# GD32F450_Power_Manager_Camera__V1_0.net
KiCad netlist of a schematic drawn in Altium Designer
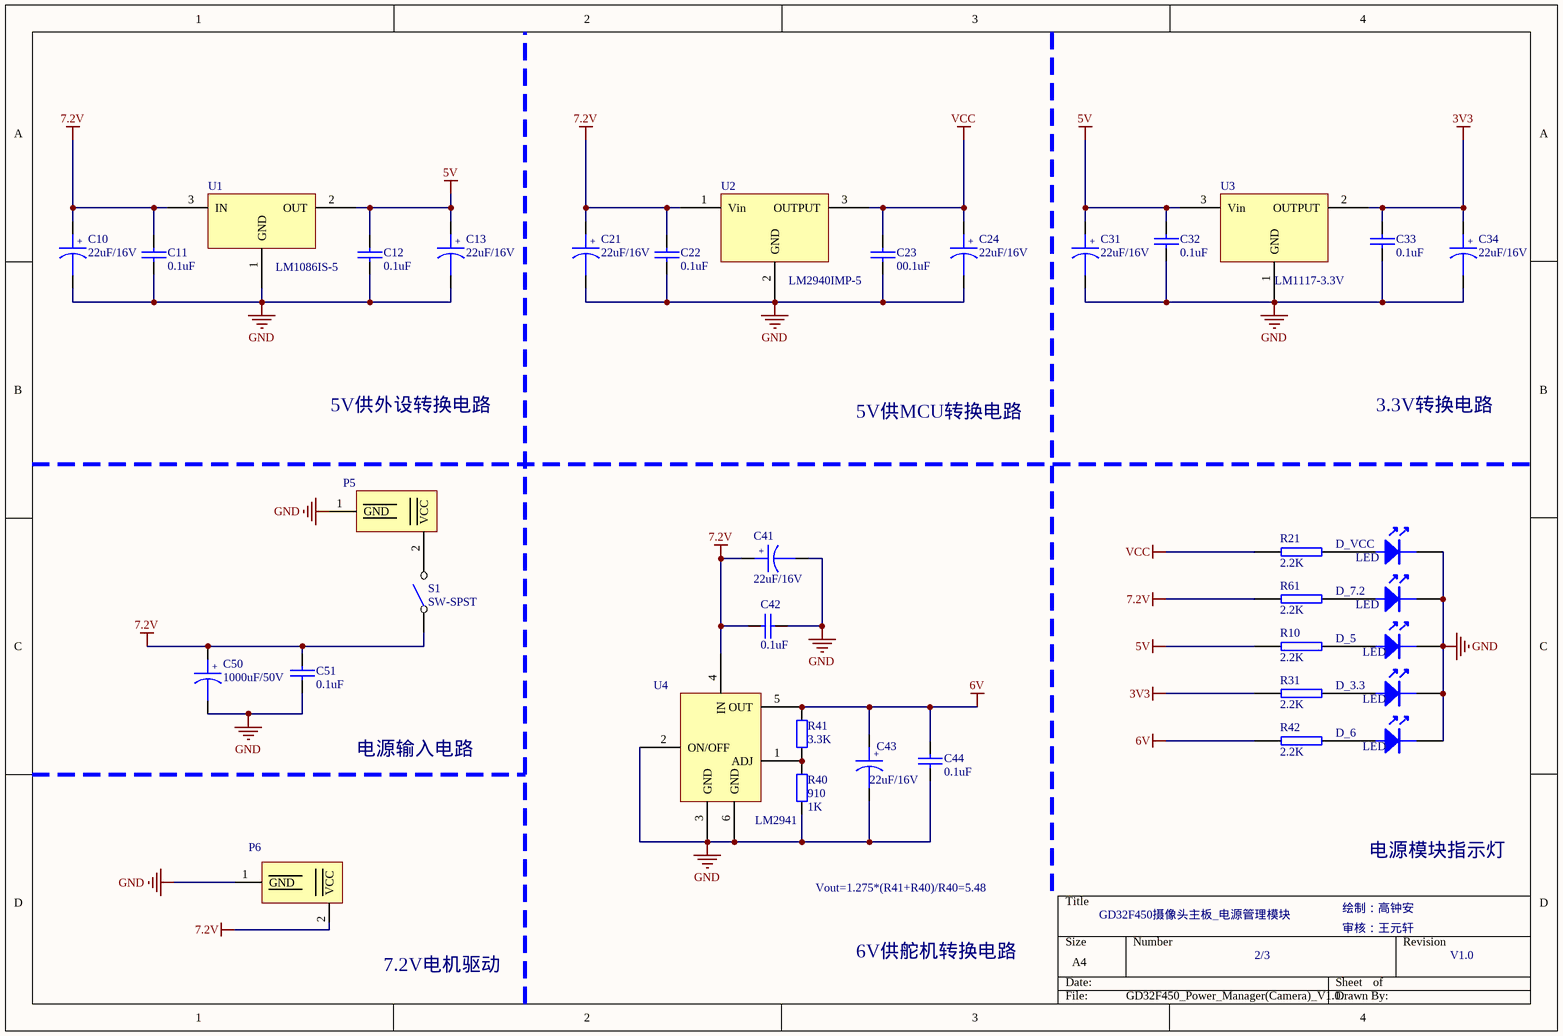
[diagram p0: GD32F450_Power_Manager(Camera)_V1.0.SchDoc]

(export (version "E")
  (design (tool "Eeschema 10.0.6"))
  (components
    (comp (ref "C10")
      (value "22uF/16V")
      (footprint "3528")
      (description "Capacitor")
      (libsource (lib "Protel99Lib_SCH") (part "CAPACITOR POL"))
    )
    (comp (ref "C11")
      (value "0.1uF")
      (footprint "0805C")
      (description "Capacitor")
      (libsource (lib "Protel99Lib_SCH") (part "CAP"))
    )
    (comp (ref "C12")
      (value "0.1uF")
      (footprint "0805C")
      (description "Capacitor")
      (libsource (lib "Protel99Lib_SCH") (part "CAP"))
    )
    (comp (ref "C13")
      (value "22uF/16V")
      (footprint "3528")
      (description "Capacitor")
      (libsource (lib "Protel99Lib_SCH") (part "CAPACITOR POL"))
    )
    (comp (ref "C21")
      (value "22uF/16V")
      (footprint "3528")
      (description "Capacitor")
      (libsource (lib "Protel99Lib_SCH") (part "CAPACITOR POL"))
    )
    (comp (ref "C22")
      (value "0.1uF")
      (footprint "0805C")
      (description "Capacitor")
      (libsource (lib "Protel99Lib_SCH") (part "CAP"))
    )
    (comp (ref "C23")
      (value "00.1uF")
      (footprint "0805C")
      (description "Capacitor")
      (libsource (lib "Protel99Lib_SCH") (part "CAP"))
    )
    (comp (ref "C24")
      (value "22uF/16V")
      (footprint "3528")
      (description "Capacitor")
      (libsource (lib "Protel99Lib_SCH") (part "CAPACITOR POL"))
    )
    (comp (ref "C31")
      (value "22uF/16V")
      (footprint "3528")
      (description "Capacitor")
      (libsource (lib "Protel99Lib_SCH") (part "CAPACITOR POL"))
    )
    (comp (ref "C32")
      (value "0.1uF")
      (footprint "0805C")
      (description "Capacitor")
      (libsource (lib "Protel99Lib_SCH") (part "CAP"))
    )
    (comp (ref "C33")
      (value "0.1uF")
      (footprint "0805C")
      (description "Capacitor")
      (libsource (lib "Protel99Lib_SCH") (part "CAP"))
    )
    (comp (ref "C34")
      (value "22uF/16V")
      (footprint "3528")
      (description "Capacitor")
      (libsource (lib "Protel99Lib_SCH") (part "CAPACITOR POL"))
    )
    (comp (ref "C41")
      (value "22uF/16V")
      (footprint "3528")
      (description "Capacitor")
      (libsource (lib "Protel99Lib_SCH") (part "CAPACITOR POL"))
    )
    (comp (ref "C42")
      (value "0.1uF")
      (footprint "0805C")
      (description "Capacitor")
      (libsource (lib "Protel99Lib_SCH") (part "CAP"))
    )
    (comp (ref "C43")
      (value "22uF/16V")
      (footprint "3528")
      (description "Capacitor")
      (libsource (lib "Protel99Lib_SCH") (part "CAPACITOR POL"))
    )
    (comp (ref "C44")
      (value "0.1uF")
      (footprint "0805C")
      (description "Capacitor")
      (libsource (lib "Protel99Lib_SCH") (part "CAP"))
    )
    (comp (ref "C50")
      (value "1000uF/50V")
      (footprint "CM F(10*10.2)")
      (description "Capacitor")
      (libsource (lib "Protel99Lib_SCH") (part "CAPACITOR POL"))
    )
    (comp (ref "C51")
      (value "0.1uF")
      (footprint "0805C")
      (description "Capacitor")
      (libsource (lib "Protel99Lib_SCH") (part "CAP"))
    )
    (comp (ref "D_3.3") (value "LED") (footprint "1206LED") (libsource (lib "Protel99Lib_SCH") (part "LED")))
    (comp (ref "D_5") (value "LED") (footprint "1206LED") (libsource (lib "Protel99Lib_SCH") (part "LED")))
    (comp (ref "D_6") (value "LED") (footprint "1206LED") (libsource (lib "Protel99Lib_SCH") (part "LED")))
    (comp (ref "D_7.2") (value "LED") (footprint "1206LED") (libsource (lib "Protel99Lib_SCH") (part "LED")))
    (comp (ref "D_VCC") (value "LED") (footprint "1206LED") (libsource (lib "Protel99Lib_SCH") (part "LED")))
    (comp (ref "P5")
      (value "T_Type_Adapter")
      (footprint "T_Type_Adapter")
      (libsource (lib "Schlib1") (part "T_Type_Adapter"))
    )
    (comp (ref "P6")
      (value "T_Type_Adapter")
      (footprint "T_Type_Adapter")
      (libsource (lib "Schlib1") (part "T_Type_Adapter"))
    )
    (comp (ref "R10") (value "2.2K") (footprint "0805R") (libsource (lib "Protel99Lib_SCH") (part "RES2")))
    (comp (ref "R21") (value "2.2K") (footprint "0805R") (libsource (lib "Protel99Lib_SCH") (part "RES2")))
    (comp (ref "R31") (value "2.2K") (footprint "0805R") (libsource (lib "Protel99Lib_SCH") (part "RES2")))
    (comp (ref "R40")
      (value "910")
      (footprint "0805")
      (description "Resistor")
      (fields (field (name "ALTIUM_VALUE") "1K") (field (name "PUBLISHER") "Altium Limited"))
      (libsource (lib "Miscellaneous Devices") (part "Res2"))
    )
    (comp (ref "R41")
      (value "3.3K")
      (footprint "0805")
      (description "Resistor")
      (fields (field (name "PUBLISHER") "Altium Limited"))
      (libsource (lib "Miscellaneous Devices") (part "Res2"))
    )
    (comp (ref "R42") (value "2.2K") (footprint "0805R") (libsource (lib "Protel99Lib_SCH") (part "RES2")))
    (comp (ref "R61") (value "2.2K") (footprint "0805R") (libsource (lib "Protel99Lib_SCH") (part "RES2")))
    (comp (ref "S1")
      (value "SW-SPST")
      (footprint "SWITCH-MINI")
      (libsource (lib "Protel99Lib_SCH") (part "SW-SPST"))
    )
    (comp (ref "U1")
      (value "LM1086IS-5")
      (footprint "TO263-3A")
      (libsource (lib "BaseLib_SCH") (part "LT1086"))
    )
    (comp (ref "U2") (value "LM2940IMP-5") (footprint "SOT-223") (libsource (lib "") (part "LM1117-3.3V_1")))
    (comp (ref "U3")
      (value "LM1117-3.3V")
      (footprint "SOT-223")
      (libsource (lib "BaseLib_SCH") (part "LM1117-3.3V"))
    )
    (comp (ref "U4")
      (value "LM2941")
      (footprint "TO-263")
      (libsource (lib "KEA128_Experiment_Platform") (part "LM2941"))
    )
  )
  (nets
    (net (code "1") (name "3V3") (class "Default")
      (node (ref "C33") (pin "1") (pinfunction "1_1") (pintype "passive"))
      (node (ref "C34") (pin "1") (pinfunction "1_1") (pintype "passive"))
      (node (ref "R31") (pin "1") (pinfunction "1_1") (pintype "passive"))
      (node (ref "U3") (pin "2") (pinfunction "OUTPUT_2") (pintype "passive"))
    )
    (net (code "2") (name "5V") (class "Default")
      (node (ref "C12") (pin "1") (pinfunction "1_1") (pintype "passive"))
      (node (ref "C13") (pin "1") (pinfunction "1_1") (pintype "passive"))
      (node (ref "C31") (pin "1") (pinfunction "1_1") (pintype "passive"))
      (node (ref "C32") (pin "1") (pinfunction "1_1") (pintype "passive"))
      (node (ref "R10") (pin "1") (pinfunction "1_1") (pintype "passive"))
      (node (ref "U1") (pin "2") (pinfunction "OUT_2") (pintype "passive"))
      (node (ref "U3") (pin "3") (pinfunction "Vin_3") (pintype "passive"))
    )
    (net (code "3") (name "6V") (class "Default")
      (node (ref "C43") (pin "1") (pinfunction "1_1") (pintype "passive"))
      (node (ref "C44") (pin "1") (pinfunction "1_1") (pintype "passive"))
      (node (ref "R41") (pin "2") (pinfunction "2_2") (pintype "passive"))
      (node (ref "R42") (pin "1") (pinfunction "1_1") (pintype "passive"))
      (node (ref "U4") (pin "5") (pinfunction "OUT_5") (pintype "passive"))
    )
    (net (code "4") (name "7.2V") (class "Default")
      (node (ref "C10") (pin "1") (pinfunction "1_1") (pintype "passive"))
      (node (ref "C11") (pin "1") (pinfunction "1_1") (pintype "passive"))
      (node (ref "C21") (pin "1") (pinfunction "1_1") (pintype "passive"))
      (node (ref "C22") (pin "1") (pinfunction "1_1") (pintype "passive"))
      (node (ref "C41") (pin "1") (pinfunction "1_1") (pintype "passive"))
      (node (ref "C42") (pin "1") (pinfunction "1_1") (pintype "passive"))
      (node (ref "C50") (pin "1") (pinfunction "1_1") (pintype "passive"))
      (node (ref "C51") (pin "1") (pinfunction "1_1") (pintype "passive"))
      (node (ref "P6") (pin "2") (pinfunction "VCC_2") (pintype "passive"))
      (node (ref "R61") (pin "1") (pinfunction "1_1") (pintype "passive"))
      (node (ref "S1") (pin "1") (pinfunction "1_1") (pintype "passive"))
      (node (ref "U1") (pin "3") (pinfunction "IN_3") (pintype "passive"))
      (node (ref "U2") (pin "1") (pinfunction "Vin_1") (pintype "passive"))
      (node (ref "U4") (pin "4") (pinfunction "IN_4") (pintype "passive"))
    )
    (net (code "5") (name "GND") (class "Default")
      (node (ref "C10") (pin "2") (pinfunction "2_2") (pintype "passive"))
      (node (ref "C11") (pin "2") (pinfunction "2_2") (pintype "passive"))
      (node (ref "C12") (pin "2") (pinfunction "2_2") (pintype "passive"))
      (node (ref "C13") (pin "2") (pinfunction "2_2") (pintype "passive"))
      (node (ref "C21") (pin "2") (pinfunction "2_2") (pintype "passive"))
      (node (ref "C22") (pin "2") (pinfunction "2_2") (pintype "passive"))
      (node (ref "C23") (pin "2") (pinfunction "2_2") (pintype "passive"))
      (node (ref "C24") (pin "2") (pinfunction "2_2") (pintype "passive"))
      (node (ref "C31") (pin "2") (pinfunction "2_2") (pintype "passive"))
      (node (ref "C32") (pin "2") (pinfunction "2_2") (pintype "passive"))
      (node (ref "C33") (pin "2") (pinfunction "2_2") (pintype "passive"))
      (node (ref "C34") (pin "2") (pinfunction "2_2") (pintype "passive"))
      (node (ref "C41") (pin "2") (pinfunction "2_2") (pintype "passive"))
      (node (ref "C42") (pin "2") (pinfunction "2_2") (pintype "passive"))
      (node (ref "C43") (pin "2") (pinfunction "2_2") (pintype "passive"))
      (node (ref "C44") (pin "2") (pinfunction "2_2") (pintype "passive"))
      (node (ref "C50") (pin "2") (pinfunction "2_2") (pintype "passive"))
      (node (ref "C51") (pin "2") (pinfunction "2_2") (pintype "passive"))
      (node (ref "D_3.3") (pin "K") (pinfunction "2_K") (pintype "passive"))
      (node (ref "D_5") (pin "K") (pinfunction "2_K") (pintype "passive"))
      (node (ref "D_6") (pin "K") (pinfunction "2_K") (pintype "passive"))
      (node (ref "D_7.2") (pin "K") (pinfunction "2_K") (pintype "passive"))
      (node (ref "D_VCC") (pin "K") (pinfunction "2_K") (pintype "passive"))
      (node (ref "P5") (pin "1") (pinfunction "GND_1") (pintype "passive"))
      (node (ref "P6") (pin "1") (pinfunction "GND_1") (pintype "passive"))
      (node (ref "R40") (pin "1") (pinfunction "1_1") (pintype "passive"))
      (node (ref "U1") (pin "1") (pinfunction "GND_1") (pintype "passive"))
      (node (ref "U2") (pin "2") (pinfunction "GND_2") (pintype "passive"))
      (node (ref "U3") (pin "1") (pinfunction "GND_1") (pintype "passive"))
      (node (ref "U4") (pin "2") (pinfunction "ON/OFF_2") (pintype "passive"))
      (node (ref "U4") (pin "3") (pinfunction "GND_3") (pintype "passive"))
      (node (ref "U4") (pin "6") (pinfunction "GND_6") (pintype "passive"))
    )
    (net (code "6") (name "Net-(D_3.3-1)") (class "Default")
      (node (ref "D_3.3") (pin "A") (pinfunction "1_A") (pintype "passive"))
      (node (ref "R31") (pin "2") (pinfunction "2_2") (pintype "passive"))
    )
    (net (code "7") (name "Net-(D_5-1)") (class "Default")
      (node (ref "D_5") (pin "A") (pinfunction "1_A") (pintype "passive"))
      (node (ref "R10") (pin "2") (pinfunction "2_2") (pintype "passive"))
    )
    (net (code "8") (name "Net-(D_6-1)") (class "Default")
      (node (ref "D_6") (pin "A") (pinfunction "1_A") (pintype "passive"))
      (node (ref "R42") (pin "2") (pinfunction "2_2") (pintype "passive"))
    )
    (net (code "9") (name "Net-(D_7.2-1)") (class "Default")
      (node (ref "D_7.2") (pin "A") (pinfunction "1_A") (pintype "passive"))
      (node (ref "R61") (pin "2") (pinfunction "2_2") (pintype "passive"))
    )
    (net (code "10") (name "Net-(D_VCC-1)") (class "Default")
      (node (ref "D_VCC") (pin "A") (pinfunction "1_A") (pintype "passive"))
      (node (ref "R21") (pin "2") (pinfunction "2_2") (pintype "passive"))
    )
    (net (code "11") (name "Net-(P5-VCC)") (class "Default")
      (node (ref "P5") (pin "2") (pinfunction "VCC_2") (pintype "passive"))
      (node (ref "S1") (pin "2") (pinfunction "2_2") (pintype "passive"))
    )
    (net (code "12") (name "Net-(U4-ADJ)") (class "Default")
      (node (ref "R40") (pin "2") (pinfunction "2_2") (pintype "passive"))
      (node (ref "R41") (pin "1") (pinfunction "1_1") (pintype "passive"))
      (node (ref "U4") (pin "1") (pinfunction "ADJ_1") (pintype "passive"))
    )
    (net (code "13") (name "VCC") (class "Default")
      (node (ref "C23") (pin "1") (pinfunction "1_1") (pintype "passive"))
      (node (ref "C24") (pin "1") (pinfunction "1_1") (pintype "passive"))
      (node (ref "R21") (pin "1") (pinfunction "1_1") (pintype "passive"))
      (node (ref "U2") (pin "3") (pinfunction "OUTPUT_3") (pintype "passive"))
    )
  )
)
